# PROC010C_Decoupling_Caps_Reference.net
KiCad netlist of a schematic drawn in Altium Designer
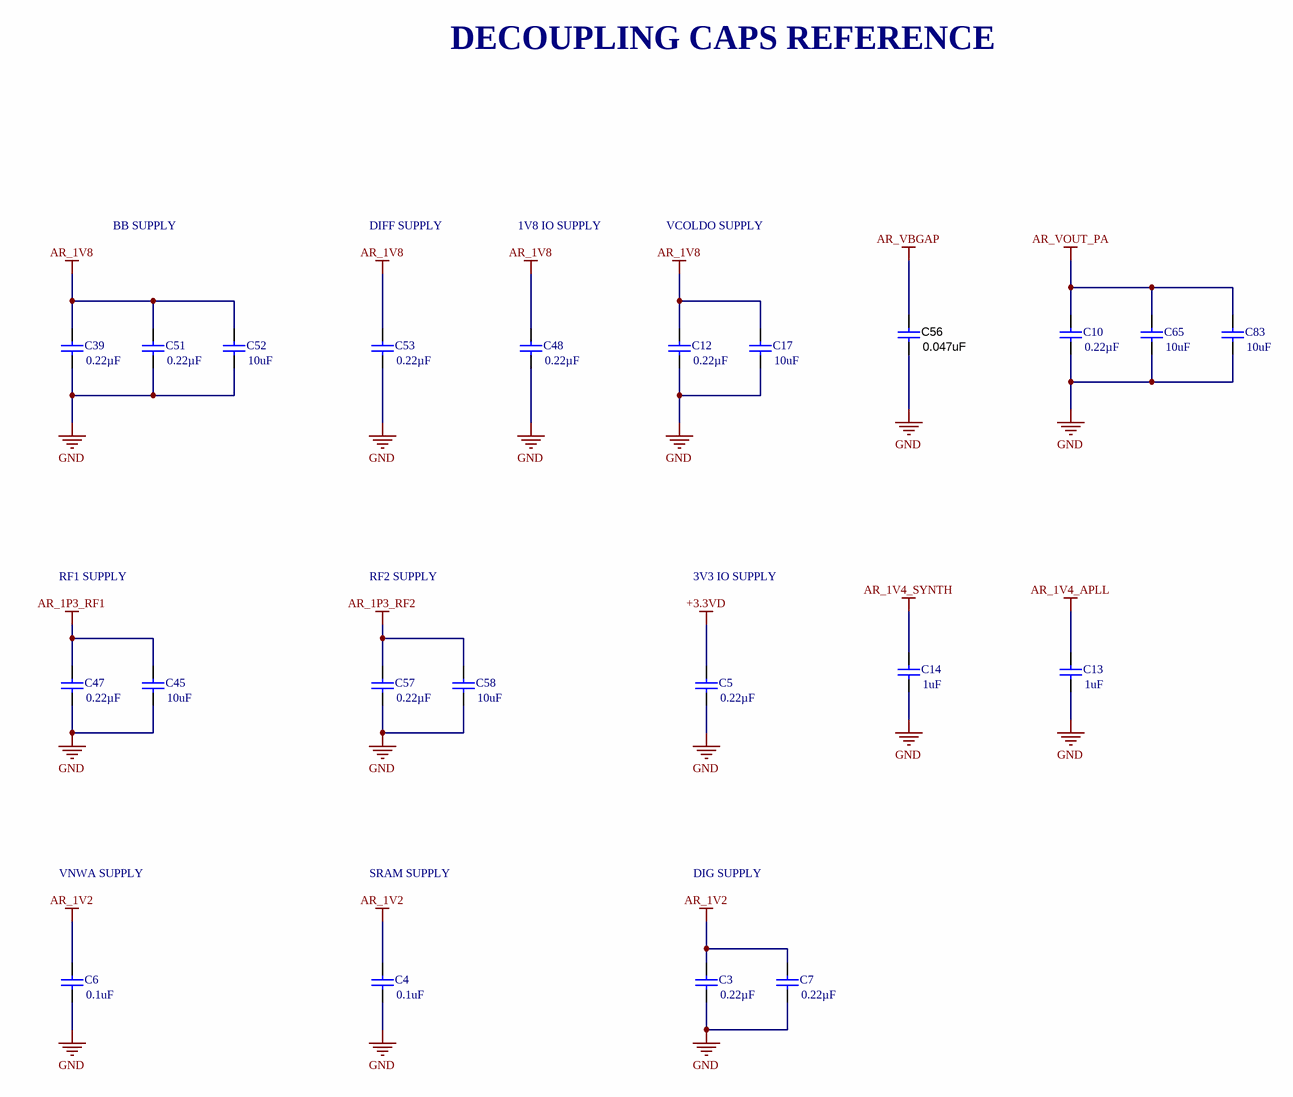
[diagram p0: PROC010C_Decoupling_Caps_Reference.SchDoc]

(export (version "E")
  (design (tool "Eeschema 10.0.6"))
  (components
    (comp (ref "C3")
      (value "GCM155R71C224KE02D")
      (footprint "0402L")
      (description "CAP, CERM, 0.22 µF, 16 V,+/- 10%, X7R, AEC-Q200 Grade 1, 0402")
      (fields (field (name "MANUFACTURER") "MuRata") (field (name "VALUEDISPLAYED") "0.22µF"))
      (libsource (lib "Altium Vault - TI") (part "CMP-0078265-1"))
    )
    (comp (ref "C4")
      (value "GCM155R71C104KA55D")
      (footprint "0402L")
      (description "CAP, CERM, 0.1 uF, 16 V, +/- 10%, X7R, 0402")
      (fields
        (field (name "MANUFACTURER") "MuRata")
        (field (name "VALUEDISPLAYED") "0.1uF")
        (field (name "PUBLISHER") "Texas Instruments")
      )
      (libsource (lib "Altium Vault - TI") (part "CMP-0006351-2"))
    )
    (comp (ref "C5")
      (value "GCM155R71C224KE02D")
      (footprint "0402L")
      (description "CAP, CERM, 0.22 µF, 16 V,+/- 10%, X7R, AEC-Q200 Grade 1, 0402")
      (fields (field (name "MANUFACTURER") "MuRata") (field (name "VALUEDISPLAYED") "0.22µF"))
      (libsource (lib "Altium Vault - TI") (part "CMP-0078265-1"))
    )
    (comp (ref "C6")
      (value "GCM155R71C104KA55D")
      (footprint "0402")
      (description "CAP, CERM, 0.1 uF, 16 V, +/- 10%, X7R, 0402")
      (fields
        (field (name "MANUFACTURER") "MuRata")
        (field (name "VALUEDISPLAYED") "0.1uF")
        (field (name "PUBLISHER") "Texas Instruments")
      )
      (libsource (lib "Altium Vault - TI") (part "Capacitor"))
    )
    (comp (ref "C7")
      (value "GCM155R71C224KE02D")
      (footprint "0402L")
      (description "CAP, CERM, 0.22 µF, 16 V,+/- 10%, X7R, AEC-Q200 Grade 1, 0402")
      (fields (field (name "MANUFACTURER") "MuRata") (field (name "VALUEDISPLAYED") "0.22µF"))
      (libsource (lib "Altium Vault - TI") (part "CMP-0078265-1"))
    )
    (comp (ref "C10")
      (value "GCM155R71C224KE02D")
      (footprint "0402")
      (description "CAP, CERM, 0.22 µF, 16 V,+/- 10%, X7R, AEC-Q200 Grade 1, 0402")
      (fields (field (name "MANUFACTURER") "MuRata") (field (name "VALUEDISPLAYED") "0.22µF"))
      (libsource (lib "Altium Vault - TI") (part "Capacitor"))
    )
    (comp (ref "C12")
      (value "GCM155R71C224KE02D")
      (footprint "0402")
      (description "CAP, CERM, 0.22 µF, 16 V,+/- 10%, X7R, AEC-Q200 Grade 1, 0402")
      (fields (field (name "MANUFACTURER") "MuRata") (field (name "VALUEDISPLAYED") "0.22µF"))
      (libsource (lib "Altium Vault - TI") (part "Capacitor"))
    )
    (comp (ref "C13")
      (value "GCM188R71C105KA64D")
      (footprint "0603")
      (description "CAP, CERM, 1 uF, 16 V, +/- 10%, X7R, AEC-Q200 Grade 1, 0603")
      (fields
        (field (name "MANUFACTURER") "MuRata")
        (field (name "VALUEDISPLAYED") "1uF")
        (field (name "PUBLISHER") "Texas Instruments")
      )
      (libsource (lib "Altium Vault - TI") (part "Capacitor"))
    )
    (comp (ref "C14")
      (value "GCM188R71C105KA64D")
      (footprint "0603")
      (description "CAP, CERM, 1 uF, 16 V, +/- 10%, X7R, AEC-Q200 Grade 1, 0603")
      (fields
        (field (name "MANUFACTURER") "MuRata")
        (field (name "VALUEDISPLAYED") "1uF")
        (field (name "PUBLISHER") "Texas Instruments")
      )
      (libsource (lib "Altium Vault - TI") (part "Capacitor"))
    )
    (comp (ref "C17")
      (value "GCM21BR71A106KE22L")
      (footprint "0805_HV")
      (description "CAP, CERM, 10 uF, 10 V, +/- 10%, X7R, 0805")
      (fields
        (field (name "MANUFACTURER") "MuRata")
        (field (name "VALUEDISPLAYED") "10uF")
        (field (name "PUBLISHER") "Texas Instruments")
      )
      (libsource (lib "Altium Vault - TI") (part "Capacitor"))
    )
    (comp (ref "C39")
      (value "GCM155R71C224KE02D")
      (footprint "0402L")
      (description "CAP, CERM, 0.22 µF, 16 V,+/- 10%, X7R, AEC-Q200 Grade 1, 0402")
      (fields (field (name "MANUFACTURER") "MuRata") (field (name "VALUEDISPLAYED") "0.22µF"))
      (libsource (lib "Altium Vault - TI") (part "CMP-0078265-1"))
    )
    (comp (ref "C45")
      (value "GCM21BR71A106KE22L")
      (footprint "0805_HV1")
      (description "CAP, CERM, 10 uF, 10 V, +/- 10%, X7R, 0805")
      (fields
        (field (name "MANUFACTURER") "MuRata")
        (field (name "VALUEDISPLAYED") "10uF")
        (field (name "PUBLISHER") "Texas Instruments")
      )
      (libsource (lib "Altium Vault - TI") (part "CMP-0008017-2"))
    )
    (comp (ref "C47")
      (value "GCM155R71C224KE02D")
      (footprint "0402L")
      (description "CAP, CERM, 0.22 µF, 16 V,+/- 10%, X7R, AEC-Q200 Grade 1, 0402")
      (fields (field (name "MANUFACTURER") "MuRata") (field (name "VALUEDISPLAYED") "0.22µF"))
      (libsource (lib "Altium Vault - TI") (part "CMP-0078265-1"))
    )
    (comp (ref "C48")
      (value "GCM155R71C224KE02D")
      (footprint "0402")
      (description "CAP, CERM, 0.22 µF, 16 V,+/- 10%, X7R, AEC-Q200 Grade 1, 0402")
      (fields (field (name "MANUFACTURER") "MuRata") (field (name "VALUEDISPLAYED") "0.22µF"))
      (libsource (lib "Altium Vault - TI") (part "Capacitor"))
    )
    (comp (ref "C51")
      (value "GCM155R71C224KE02D")
      (footprint "0402")
      (description "CAP, CERM, 0.22 µF, 16 V,+/- 10%, X7R, AEC-Q200 Grade 1, 0402")
      (fields (field (name "MANUFACTURER") "MuRata") (field (name "VALUEDISPLAYED") "0.22µF"))
      (libsource (lib "Altium Vault - TI") (part "Capacitor"))
    )
    (comp (ref "C52")
      (value "GCM21BR71A106KE22L")
      (footprint "0805_HV")
      (description "CAP, CERM, 10 uF, 10 V, +/- 10%, X7R, 0805")
      (fields
        (field (name "MANUFACTURER") "MuRata")
        (field (name "VALUEDISPLAYED") "10uF")
        (field (name "PUBLISHER") "Texas Instruments")
      )
      (libsource (lib "Altium Vault - TI") (part "Capacitor"))
    )
    (comp (ref "C53")
      (value "GCM155R71C224KE02D")
      (footprint "0402")
      (description "CAP, CERM, 0.22 µF, 16 V,+/- 10%, X7R, AEC-Q200 Grade 1, 0402")
      (fields (field (name "MANUFACTURER") "MuRata") (field (name "VALUEDISPLAYED") "0.22µF"))
      (libsource (lib "Altium Vault - TI") (part "Capacitor"))
    )
    (comp (ref "C56")
      (value "CGA2B3X7R1H473K050BB")
      (footprint "0402")
      (description "CAP, CERM, 0.047 uF, 50 V, +/- 10%, X7R, AEC-Q200 Grade 1, 0402")
      (fields
        (field (name "MANUFACTURER") "TDK")
        (field (name "VALUEDISPLAYED") "0.047uF")
        (field (name "PUBLISHER") "Texas Instruments")
      )
      (libsource (lib "Altium Vault - TI") (part "Capacitor"))
    )
    (comp (ref "C57")
      (value "GCM155R71C224KE02D")
      (footprint "0402")
      (description "CAP, CERM, 0.22 µF, 16 V,+/- 10%, X7R, AEC-Q200 Grade 1, 0402")
      (fields (field (name "MANUFACTURER") "MuRata") (field (name "VALUEDISPLAYED") "0.22µF"))
      (libsource (lib "Altium Vault - TI") (part "Capacitor"))
    )
    (comp (ref "C58")
      (value "GCM21BR71A106KE22L")
      (footprint "0805")
      (description "CAP, CERM, 10 uF, 10 V, +/- 10%, X7R, 0805")
      (fields
        (field (name "MANUFACTURER") "MuRata")
        (field (name "VALUEDISPLAYED") "10uF")
        (field (name "PUBLISHER") "Texas Instruments")
      )
      (libsource (lib "Altium Vault - TI") (part "CMP-0008017-2"))
    )
    (comp (ref "C65")
      (value "GCM21BR71A106KE22L")
      (footprint "0805_HV")
      (description "CAP, CERM, 10 uF, 10 V, +/- 10%, X7R, 0805")
      (fields
        (field (name "MANUFACTURER") "MuRata")
        (field (name "VALUEDISPLAYED") "10uF")
        (field (name "PUBLISHER") "Texas Instruments")
      )
      (libsource (lib "Altium Vault - TI") (part "Capacitor"))
    )
    (comp (ref "C83")
      (value "GCM21BR71A106KE22L")
      (footprint "0805_HV")
      (description "CAP, CERM, 10 uF, 10 V, +/- 10%, X7R, 0805")
      (fields
        (field (name "MANUFACTURER") "MuRata")
        (field (name "VALUEDISPLAYED") "10uF")
        (field (name "PUBLISHER") "Texas Instruments")
      )
      (libsource (lib "Altium Vault - TI") (part "Capacitor"))
    )
  )
  (nets
    (net (code "1") (name "+3.3VD") (class "Default")
      (node (ref "C5") (pin "1") (pinfunction "1_1") (pintype "passive"))
    )
    (net (code "2") (name "AR_1P3_RF1") (class "Default")
      (node (ref "C45") (pin "1") (pinfunction "1_1") (pintype "passive"))
      (node (ref "C47") (pin "1") (pinfunction "1_1") (pintype "passive"))
    )
    (net (code "3") (name "AR_1P3_RF2") (class "Default")
      (node (ref "C57") (pin "1") (pinfunction "1_1") (pintype "passive"))
      (node (ref "C58") (pin "1") (pinfunction "1_1") (pintype "passive"))
    )
    (net (code "4") (name "AR_1V2") (class "Default")
      (node (ref "C3") (pin "1") (pinfunction "1_1") (pintype "passive"))
      (node (ref "C4") (pin "1") (pinfunction "1_1") (pintype "passive"))
      (node (ref "C6") (pin "1") (pinfunction "1_1") (pintype "passive"))
      (node (ref "C7") (pin "1") (pinfunction "1_1") (pintype "passive"))
    )
    (net (code "5") (name "AR_1V4_APLL") (class "Default")
      (node (ref "C13") (pin "1") (pinfunction "1_1") (pintype "passive"))
    )
    (net (code "6") (name "AR_1V4_SYNTH") (class "Default")
      (node (ref "C14") (pin "1") (pinfunction "1_1") (pintype "passive"))
    )
    (net (code "7") (name "AR_1V8") (class "Default")
      (node (ref "C12") (pin "1") (pinfunction "1_1") (pintype "passive"))
      (node (ref "C17") (pin "1") (pinfunction "1_1") (pintype "passive"))
      (node (ref "C39") (pin "1") (pinfunction "1_1") (pintype "passive"))
      (node (ref "C48") (pin "1") (pinfunction "1_1") (pintype "passive"))
      (node (ref "C51") (pin "1") (pinfunction "1_1") (pintype "passive"))
      (node (ref "C52") (pin "1") (pinfunction "1_1") (pintype "passive"))
      (node (ref "C53") (pin "1") (pinfunction "1_1") (pintype "passive"))
    )
    (net (code "8") (name "AR_VBGAP") (class "Default")
      (node (ref "C56") (pin "1") (pinfunction "1_1") (pintype "passive"))
    )
    (net (code "9") (name "AR_VOUT_PA") (class "Default")
      (node (ref "C10") (pin "1") (pinfunction "1_1") (pintype "passive"))
      (node (ref "C65") (pin "1") (pinfunction "1_1") (pintype "passive"))
      (node (ref "C83") (pin "1") (pinfunction "1_1") (pintype "passive"))
    )
    (net (code "10") (name "GND") (class "Default")
      (node (ref "C10") (pin "2") (pinfunction "2_2") (pintype "passive"))
      (node (ref "C12") (pin "2") (pinfunction "2_2") (pintype "passive"))
      (node (ref "C13") (pin "2") (pinfunction "2_2") (pintype "passive"))
      (node (ref "C14") (pin "2") (pinfunction "2_2") (pintype "passive"))
      (node (ref "C17") (pin "2") (pinfunction "2_2") (pintype "passive"))
      (node (ref "C3") (pin "2") (pinfunction "2_2") (pintype "passive"))
      (node (ref "C39") (pin "2") (pinfunction "2_2") (pintype "passive"))
      (node (ref "C4") (pin "2") (pinfunction "2_2") (pintype "passive"))
      (node (ref "C45") (pin "2") (pinfunction "2_2") (pintype "passive"))
      (node (ref "C47") (pin "2") (pinfunction "2_2") (pintype "passive"))
      (node (ref "C48") (pin "2") (pinfunction "2_2") (pintype "passive"))
      (node (ref "C5") (pin "2") (pinfunction "2_2") (pintype "passive"))
      (node (ref "C51") (pin "2") (pinfunction "2_2") (pintype "passive"))
      (node (ref "C52") (pin "2") (pinfunction "2_2") (pintype "passive"))
      (node (ref "C53") (pin "2") (pinfunction "2_2") (pintype "passive"))
      (node (ref "C56") (pin "2") (pinfunction "2_2") (pintype "passive"))
      (node (ref "C57") (pin "2") (pinfunction "2_2") (pintype "passive"))
      (node (ref "C58") (pin "2") (pinfunction "2_2") (pintype "passive"))
      (node (ref "C6") (pin "2") (pinfunction "2_2") (pintype "passive"))
      (node (ref "C65") (pin "2") (pinfunction "2_2") (pintype "passive"))
      (node (ref "C7") (pin "2") (pinfunction "2_2") (pintype "passive"))
      (node (ref "C83") (pin "2") (pinfunction "2_2") (pintype "passive"))
    )
  )
)
